# Optostop.net
KiCad netlist of a schematic drawn in EAGLE
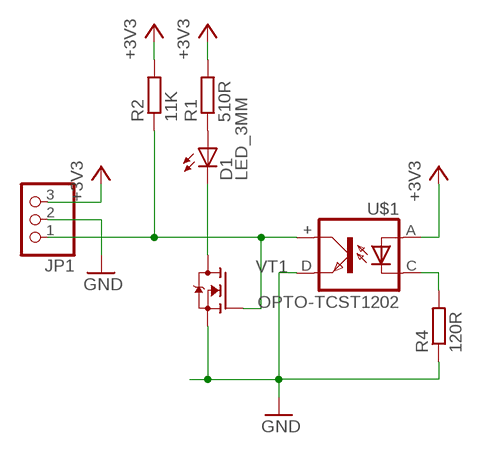
[diagram p0: schematic, sheet 1]

(export (version "E")
  (design (tool "Eeschema 10.0.6"))
  (components
    (comp (ref "D1")
      (value "LED_3MM")
      (footprint "eagle-import:LED3MM")
      (libsource (lib "eagle-import") (part "LED_3MM"))
    )
    (comp (ref "JP1")
      (value "PINHD-1X3/90")
      (footprint "eagle-import:1X03_90")
      (libsource (lib "eagle-import") (part "PINHD-1X3/90"))
    )
    (comp (ref "R1")
      (value "510R")
      (footprint "eagle-import:R0805")
      (libsource (lib "eagle-import") (part "R_0805"))
    )
    (comp (ref "R2")
      (value "11K")
      (footprint "eagle-import:R0805")
      (libsource (lib "eagle-import") (part "R_0805"))
    )
    (comp (ref "R4")
      (value "120R")
      (footprint "eagle-import:R0805")
      (libsource (lib "eagle-import") (part "R_0805"))
    )
    (comp (ref "U$1")
      (value "OPTO-TCST1202")
      (footprint "eagle-import:TCST1202")
      (libsource (lib "eagle-import") (part "OPTO-TCST1202"))
    )
    (comp (ref "VT1")
      (value "FET-NSOT-23")
      (footprint "eagle-import:SOT23")
      (libsource (lib "eagle-import") (part "FET-NSOT-23"))
    )
  )
  (nets
    (net (code "1") (name "+3V3") (class "Default")
      (node (ref "JP1") (pin "3") (pinfunction "3_3") (pintype "passive"))
      (node (ref "R1") (pin "2") (pinfunction "2_2") (pintype "passive"))
      (node (ref "R2") (pin "2") (pinfunction "2_2") (pintype "passive"))
      (node (ref "U$1") (pin "A") (pinfunction "A_A") (pintype "passive"))
    )
    (net (code "2") (name "GND") (class "Default")
      (node (ref "JP1") (pin "2") (pinfunction "2_2") (pintype "passive"))
      (node (ref "R4") (pin "1") (pinfunction "1_1") (pintype "passive"))
      (node (ref "U$1") (pin "D") (pinfunction "EMIT_D") (pintype "passive"))
      (node (ref "VT1") (pin "2") (pinfunction "S_2") (pintype "passive"))
    )
    (net (code "3") (name "Net-(D1-C)") (class "Default")
      (node (ref "D1") (pin "K") (pinfunction "C_K") (pintype "passive"))
      (node (ref "VT1") (pin "3") (pinfunction "D_3") (pintype "passive"))
    )
    (net (code "4") (name "Net-(D1-PadA)") (class "Default")
      (node (ref "D1") (pin "A") (pinfunction "A_A") (pintype "passive"))
      (node (ref "R1") (pin "1") (pinfunction "1_1") (pintype "passive"))
    )
    (net (code "5") (name "Net-(R4-Pad2)") (class "Default")
      (node (ref "R4") (pin "2") (pinfunction "2_2") (pintype "passive"))
      (node (ref "U$1") (pin "C") (pinfunction "C_C") (pintype "passive"))
    )
    (net (code "6") (name "Net-(U$1-COL)") (class "Default")
      (node (ref "JP1") (pin "1") (pinfunction "1_1") (pintype "passive"))
      (node (ref "R2") (pin "1") (pinfunction "1_1") (pintype "passive"))
      (node (ref "U$1") (pin "+") (pinfunction "COL_+") (pintype "passive"))
      (node (ref "VT1") (pin "1") (pinfunction "G_1") (pintype "passive"))
    )
  )
)
